# Gameboy_Pocket.net
KiCad netlist of a schematic drawn in EAGLE
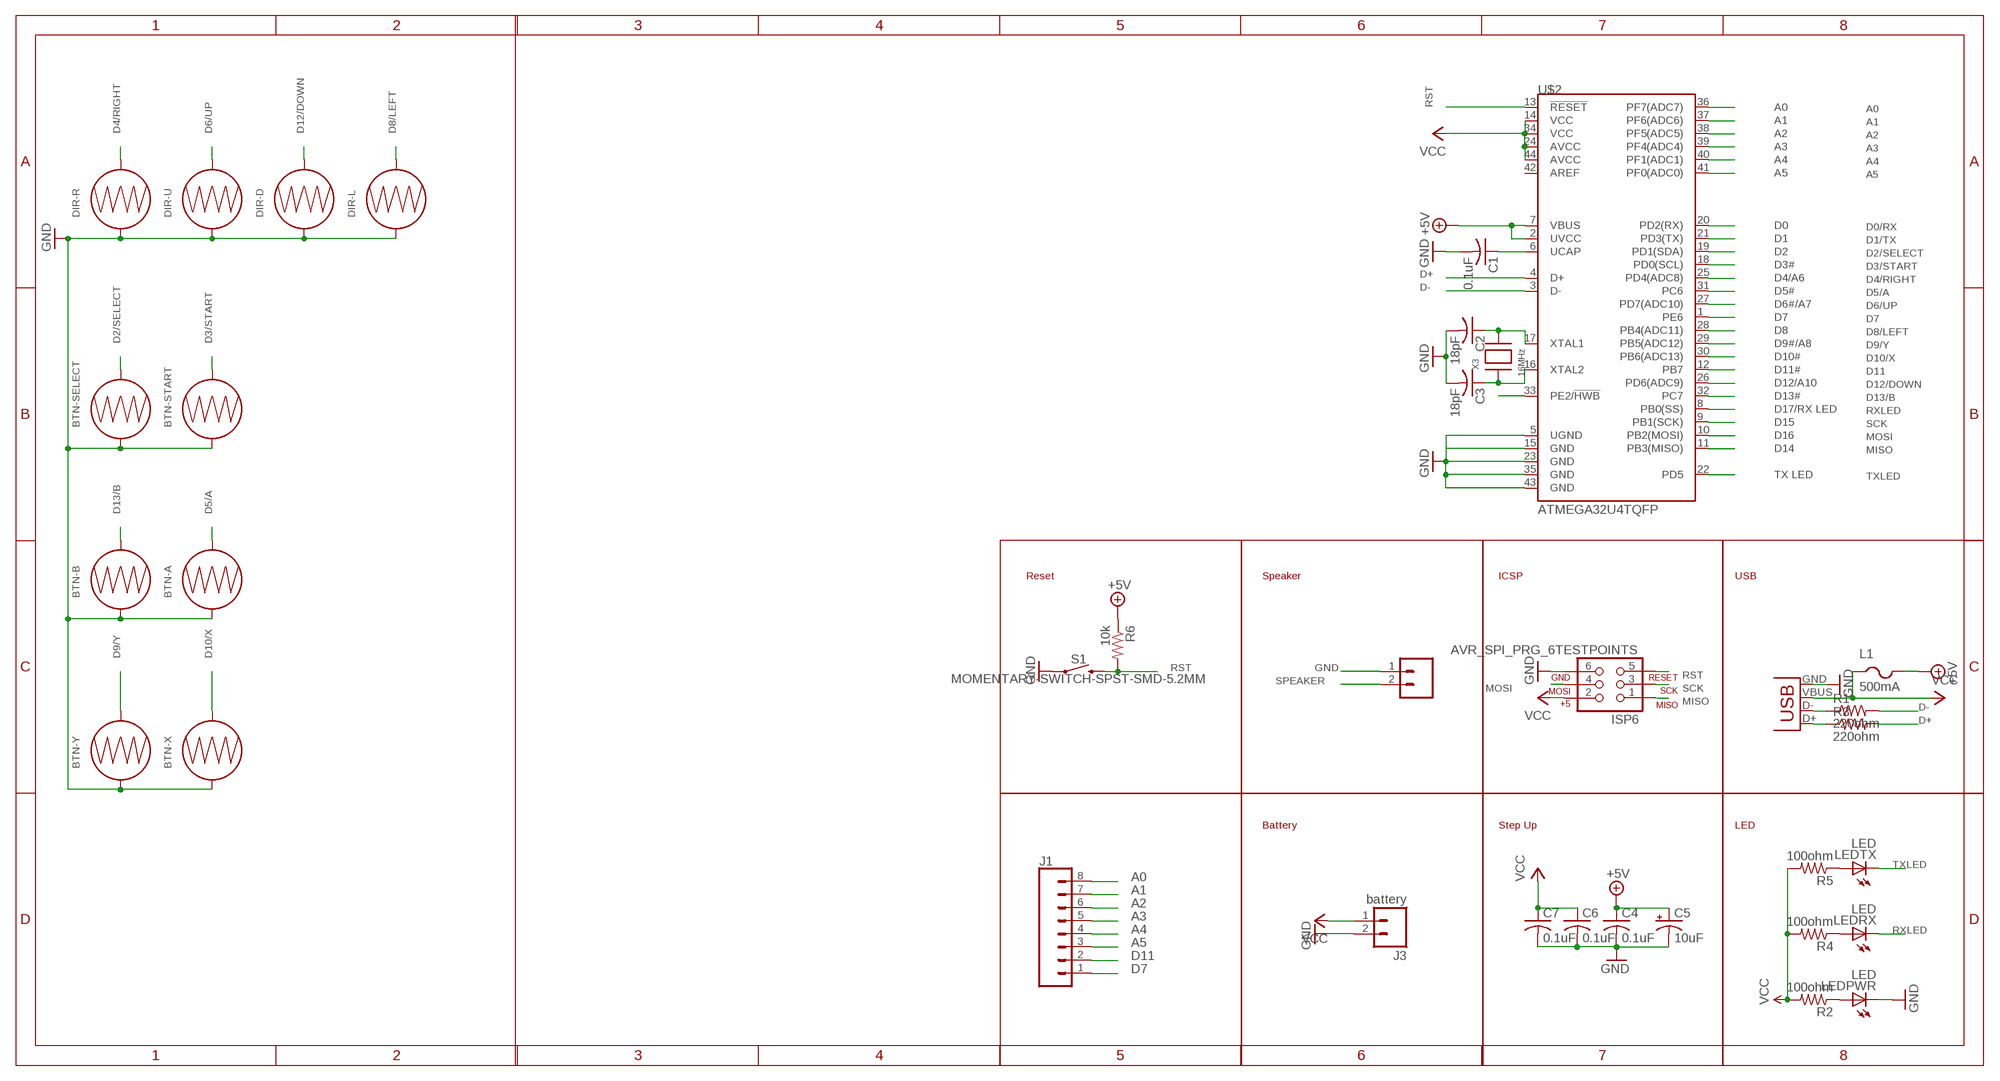
[diagram p0: schematic, sheet 1]

(export (version "E")
  (design (tool "Eeschema 10.0.6"))
  (components
    (comp (ref "BTN-A")
      (value "BUTTON-CONDUCTIVESMD")
      (footprint "eagle-import:BUTTON-CONDUCTIVE")
      (libsource (lib "eagle-import") (part "BUTTON-CONDUCTIVESMD"))
    )
    (comp (ref "BTN-B")
      (value "BUTTON-CONDUCTIVESMD")
      (footprint "eagle-import:BUTTON-CONDUCTIVE")
      (libsource (lib "eagle-import") (part "BUTTON-CONDUCTIVESMD"))
    )
    (comp (ref "BTN-SELECT")
      (value "BUTTON-CONDUCTIVESMD")
      (footprint "eagle-import:BUTTON-CONDUCTIVE")
      (libsource (lib "eagle-import") (part "BUTTON-CONDUCTIVESMD"))
    )
    (comp (ref "BTN-START")
      (value "BUTTON-CONDUCTIVESMD")
      (footprint "eagle-import:BUTTON-CONDUCTIVE")
      (libsource (lib "eagle-import") (part "BUTTON-CONDUCTIVESMD"))
    )
    (comp (ref "BTN-X")
      (value "BUTTON-CONDUCTIVESMD")
      (footprint "eagle-import:BUTTON-CONDUCTIVE")
      (libsource (lib "eagle-import") (part "BUTTON-CONDUCTIVESMD"))
    )
    (comp (ref "BTN-Y")
      (value "BUTTON-CONDUCTIVESMD")
      (footprint "eagle-import:BUTTON-CONDUCTIVE")
      (libsource (lib "eagle-import") (part "BUTTON-CONDUCTIVESMD"))
    )
    (comp (ref "C1")
      (value "0.1uF")
      (footprint "eagle-import:C0805")
      (libsource (lib "eagle-import") (part "C-USC0805"))
    )
    (comp (ref "C2")
      (value "18pF")
      (footprint "eagle-import:C0805")
      (libsource (lib "eagle-import") (part "C-USC0805"))
    )
    (comp (ref "C3")
      (value "18pF")
      (footprint "eagle-import:C0805")
      (libsource (lib "eagle-import") (part "C-USC0805"))
    )
    (comp (ref "C4")
      (value "0.1uF")
      (footprint "eagle-import:C0805")
      (libsource (lib "eagle-import") (part "C-USC0805"))
    )
    (comp (ref "C5")
      (value "10uF")
      (footprint "eagle-import:EIA3216")
      (libsource (lib "eagle-import") (part "10UF-TANT"))
    )
    (comp (ref "C6")
      (value "0.1uF")
      (footprint "eagle-import:C0805")
      (libsource (lib "eagle-import") (part "C-USC0805"))
    )
    (comp (ref "C7")
      (value "0.1uF")
      (footprint "eagle-import:C0805")
      (libsource (lib "eagle-import") (part "C-USC0805"))
    )
    (comp (ref "CN1")
      (value "USB-SMD-NS")
      (footprint "eagle-import:USB-MINIB-NOSTOP")
      (libsource (lib "eagle-import") (part "USB-SMD-NS"))
    )
    (comp (ref "DIR-D")
      (value "BUTTON-CONDUCTIVESMD")
      (footprint "eagle-import:BUTTON-CONDUCTIVE")
      (libsource (lib "eagle-import") (part "BUTTON-CONDUCTIVESMD"))
    )
    (comp (ref "DIR-L")
      (value "BUTTON-CONDUCTIVESMD")
      (footprint "eagle-import:BUTTON-CONDUCTIVE")
      (libsource (lib "eagle-import") (part "BUTTON-CONDUCTIVESMD"))
    )
    (comp (ref "DIR-R")
      (value "BUTTON-CONDUCTIVESMD")
      (footprint "eagle-import:BUTTON-CONDUCTIVE")
      (libsource (lib "eagle-import") (part "BUTTON-CONDUCTIVESMD"))
    )
    (comp (ref "DIR-U")
      (value "BUTTON-CONDUCTIVESMD")
      (footprint "eagle-import:BUTTON-CONDUCTIVE")
      (libsource (lib "eagle-import") (part "BUTTON-CONDUCTIVESMD"))
    )
    (comp (ref "ISP6")
      (value "AVR_SPI_PRG_6TESTPOINTS")
      (footprint "eagle-import:2X3_TEST_POINTS")
      (libsource (lib "eagle-import") (part "AVR_SPI_PRG_6TESTPOINTS"))
    )
    (comp (ref "J1")
      (value "CONN_08NO_SILK_FEMALE_PTH")
      (footprint "eagle-import:1X08_NO_SILK")
      (libsource (lib "eagle-import") (part "CONN_08NO_SILK_FEMALE_PTH"))
    )
    (comp (ref "J3")
      (value "battery")
      (footprint "eagle-import:JST-2-PTH-VERT")
      (libsource (lib "eagle-import") (part "M02JST-PTH-VERT"))
    )
    (comp (ref "JP2")
      (value "M02PTH")
      (footprint "eagle-import:1X02")
      (libsource (lib "eagle-import") (part "M02PTH"))
    )
    (comp (ref "L1")
      (value "500mA")
      (footprint "eagle-import:R1206")
      (libsource (lib "eagle-import") (part "PTCFUSE-1206"))
    )
    (comp (ref "LEDPWR")
      (value "LED")
      (footprint "eagle-import:CHIPLED_0805")
      (libsource (lib "eagle-import") (part "LEDCHIPLED_0805"))
    )
    (comp (ref "LEDRX")
      (value "LED")
      (footprint "eagle-import:CHIPLED_0805")
      (libsource (lib "eagle-import") (part "LEDCHIPLED_0805"))
    )
    (comp (ref "LEDTX")
      (value "LED")
      (footprint "eagle-import:CHIPLED_0805")
      (libsource (lib "eagle-import") (part "LEDCHIPLED_0805"))
    )
    (comp (ref "R1")
      (value "220ohm")
      (footprint "eagle-import:R0805")
      (libsource (lib "eagle-import") (part "R-US_R0805"))
    )
    (comp (ref "R2")
      (value "100ohm")
      (footprint "eagle-import:R0805")
      (libsource (lib "eagle-import") (part "R-US_R0805"))
    )
    (comp (ref "R3")
      (value "220ohm")
      (footprint "eagle-import:R0805")
      (libsource (lib "eagle-import") (part "R-US_R0805"))
    )
    (comp (ref "R4")
      (value "100ohm")
      (footprint "eagle-import:R0805")
      (libsource (lib "eagle-import") (part "R-US_R0805"))
    )
    (comp (ref "R5")
      (value "100ohm")
      (footprint "eagle-import:R0805")
      (libsource (lib "eagle-import") (part "R-US_R0805"))
    )
    (comp (ref "R6")
      (value "10k")
      (footprint "eagle-import:R0805")
      (libsource (lib "eagle-import") (part "R-US_R0805"))
    )
    (comp (ref "S1")
      (value "MOMENTARY-SWITCH-SPST-SMD-5.2MM")
      (footprint "eagle-import:TACTILE_SWITCH_SMD_5.2MM")
      (libsource (lib "eagle-import") (part "MOMENTARY-SWITCH-SPST-SMD-5.2MM"))
    )
    (comp (ref "U$2")
      (value "ATMEGA32U4TQFP")
      (footprint "eagle-import:SPARKFUN-DIGITALIC_TQFP44")
      (libsource (lib "eagle-import") (part "ATMEGA32U4TQFP"))
    )
    (comp (ref "X3")
      (value "16MHz")
      (footprint "eagle-import:NX5032")
      (libsource (lib "eagle-import") (part "XTALNX5032"))
    )
  )
  (nets
    (net (code "1") (name "+5V") (class "Default")
      (node (ref "C4") (pin "1") (pinfunction "1_1") (pintype "passive"))
      (node (ref "C5") (pin "A") (pinfunction "+_A") (pintype "passive"))
      (node (ref "L1") (pin "2") (pinfunction "2_2") (pintype "passive"))
      (node (ref "R6") (pin "1") (pinfunction "1_1") (pintype "passive"))
      (node (ref "U$2") (pin "2") (pinfunction "UVCC_2") (pintype "bidirectional"))
      (node (ref "U$2") (pin "7") (pinfunction "VBUS_7") (pintype "bidirectional"))
    )
    (net (code "2") (name "/A0") (class "Default")
      (node (ref "J1") (pin "8") (pinfunction "8_8") (pintype "passive"))
      (node (ref "U$2") (pin "36") (pinfunction "PF7(ADC7)_36") (pintype "bidirectional"))
    )
    (net (code "3") (name "/A1") (class "Default")
      (node (ref "J1") (pin "7") (pinfunction "7_7") (pintype "passive"))
      (node (ref "U$2") (pin "37") (pinfunction "PF6(ADC6)_37") (pintype "bidirectional"))
    )
    (net (code "4") (name "/A2") (class "Default")
      (node (ref "J1") (pin "6") (pinfunction "6_6") (pintype "passive"))
      (node (ref "U$2") (pin "38") (pinfunction "PF5(ADC5)_38") (pintype "bidirectional"))
    )
    (net (code "5") (name "/A3") (class "Default")
      (node (ref "J1") (pin "5") (pinfunction "5_5") (pintype "passive"))
      (node (ref "U$2") (pin "39") (pinfunction "PF4(ADC4)_39") (pintype "bidirectional"))
    )
    (net (code "6") (name "/A4") (class "Default")
      (node (ref "J1") (pin "4") (pinfunction "4_4") (pintype "passive"))
      (node (ref "U$2") (pin "40") (pinfunction "PF1(ADC1)_40") (pintype "bidirectional"))
    )
    (net (code "7") (name "/A5") (class "Default")
      (node (ref "J1") (pin "3") (pinfunction "3_3") (pintype "passive"))
      (node (ref "U$2") (pin "41") (pinfunction "PF0(ADC0)_41") (pintype "bidirectional"))
    )
    (net (code "8") (name "/D+") (class "Default")
      (node (ref "R3") (pin "2") (pinfunction "2_2") (pintype "passive"))
      (node (ref "U$2") (pin "4") (pinfunction "D+_4") (pintype "bidirectional"))
    )
    (net (code "9") (name "/D-") (class "Default")
      (node (ref "R1") (pin "2") (pinfunction "2_2") (pintype "passive"))
      (node (ref "U$2") (pin "3") (pinfunction "D-_3") (pintype "bidirectional"))
    )
    (net (code "10") (name "/D0{slash}RX") (class "Default")
      (node (ref "U$2") (pin "20") (pinfunction "PD2(RX)_20") (pintype "bidirectional"))
    )
    (net (code "11") (name "/D1{slash}TX") (class "Default")
      (node (ref "U$2") (pin "21") (pinfunction "PD3(TX)_21") (pintype "bidirectional"))
    )
    (net (code "12") (name "/D2{slash}SELECT") (class "Default")
      (node (ref "BTN-SELECT") (pin "2") (pinfunction "2_2") (pintype "passive"))
      (node (ref "U$2") (pin "19") (pinfunction "PD1(SDA)_19") (pintype "bidirectional"))
    )
    (net (code "13") (name "/D3{slash}START") (class "Default")
      (node (ref "BTN-START") (pin "2") (pinfunction "2_2") (pintype "passive"))
      (node (ref "U$2") (pin "18") (pinfunction "PD0(SCL)_18") (pintype "bidirectional"))
    )
    (net (code "14") (name "/D4{slash}RIGHT") (class "Default")
      (node (ref "DIR-R") (pin "2") (pinfunction "2_2") (pintype "passive"))
      (node (ref "U$2") (pin "25") (pinfunction "PD4(ADC8)_25") (pintype "bidirectional"))
    )
    (net (code "15") (name "/D5{slash}A") (class "Default")
      (node (ref "BTN-A") (pin "2") (pinfunction "2_2") (pintype "passive"))
      (node (ref "U$2") (pin "31") (pinfunction "PC6_31") (pintype "bidirectional"))
    )
    (net (code "16") (name "/D6{slash}UP") (class "Default")
      (node (ref "DIR-U") (pin "2") (pinfunction "2_2") (pintype "passive"))
      (node (ref "U$2") (pin "27") (pinfunction "PD7(ADC10)_27") (pintype "bidirectional"))
    )
    (net (code "17") (name "/D7") (class "Default")
      (node (ref "J1") (pin "1") (pinfunction "1_1") (pintype "passive"))
      (node (ref "U$2") (pin "1") (pinfunction "PE6_1") (pintype "bidirectional"))
    )
    (net (code "18") (name "/D8{slash}LEFT") (class "Default")
      (node (ref "DIR-L") (pin "2") (pinfunction "2_2") (pintype "passive"))
      (node (ref "U$2") (pin "28") (pinfunction "PB4(ADC11)_28") (pintype "bidirectional"))
    )
    (net (code "19") (name "/D9{slash}Y") (class "Default")
      (node (ref "BTN-Y") (pin "2") (pinfunction "2_2") (pintype "passive"))
      (node (ref "U$2") (pin "29") (pinfunction "PB5(ADC12)_29") (pintype "bidirectional"))
    )
    (net (code "20") (name "/D10{slash}X") (class "Default")
      (node (ref "BTN-X") (pin "2") (pinfunction "2_2") (pintype "passive"))
      (node (ref "U$2") (pin "30") (pinfunction "PB6(ADC13)_30") (pintype "bidirectional"))
    )
    (net (code "21") (name "/D11") (class "Default")
      (node (ref "J1") (pin "2") (pinfunction "2_2") (pintype "passive"))
      (node (ref "U$2") (pin "12") (pinfunction "PB7_12") (pintype "bidirectional"))
    )
    (net (code "22") (name "/D12{slash}DOWN") (class "Default")
      (node (ref "DIR-D") (pin "2") (pinfunction "2_2") (pintype "passive"))
      (node (ref "U$2") (pin "26") (pinfunction "PD6(ADC9)_26") (pintype "bidirectional"))
    )
    (net (code "23") (name "/D13{slash}B") (class "Default")
      (node (ref "BTN-B") (pin "2") (pinfunction "2_2") (pintype "passive"))
      (node (ref "U$2") (pin "32") (pinfunction "PC7_32") (pintype "bidirectional"))
    )
    (net (code "24") (name "/MISO") (class "Default")
      (node (ref "ISP6") (pin "1") (pinfunction "1_1") (pintype "passive"))
      (node (ref "U$2") (pin "11") (pinfunction "PB3(MISO)_11") (pintype "bidirectional"))
    )
    (net (code "25") (name "/MOSI") (class "Default")
      (node (ref "ISP6") (pin "4") (pinfunction "4_4") (pintype "passive"))
      (node (ref "U$2") (pin "10") (pinfunction "PB2(MOSI)_10") (pintype "bidirectional"))
    )
    (net (code "26") (name "/RST") (class "Default")
      (node (ref "ISP6") (pin "5") (pinfunction "5_5") (pintype "passive"))
      (node (ref "R6") (pin "2") (pinfunction "2_2") (pintype "passive"))
      (node (ref "S1") (pin "3") (pinfunction "2_3") (pintype "passive"))
      (node (ref "U$2") (pin "13") (pinfunction "~{RESET}_13") (pintype "bidirectional"))
    )
    (net (code "27") (name "/RXLED") (class "Default")
      (node (ref "LEDRX") (pin "C") (pinfunction "C_C") (pintype "passive"))
      (node (ref "U$2") (pin "8") (pinfunction "PB0(SS)_8") (pintype "bidirectional"))
    )
    (net (code "28") (name "/SCK") (class "Default")
      (node (ref "ISP6") (pin "3") (pinfunction "3_3") (pintype "passive"))
      (node (ref "U$2") (pin "9") (pinfunction "PB1(SCK)_9") (pintype "bidirectional"))
    )
    (net (code "29") (name "/SPEAKER") (class "Default")
      (node (ref "JP2") (pin "2") (pinfunction "2_2") (pintype "passive"))
    )
    (net (code "30") (name "/TXLED") (class "Default")
      (node (ref "LEDTX") (pin "C") (pinfunction "C_C") (pintype "passive"))
      (node (ref "U$2") (pin "22") (pinfunction "PD5_22") (pintype "bidirectional"))
    )
    (net (code "31") (name "GND") (class "Default")
      (node (ref "BTN-A") (pin "1") (pinfunction "1_1") (pintype "passive"))
      (node (ref "BTN-B") (pin "1") (pinfunction "1_1") (pintype "passive"))
      (node (ref "BTN-SELECT") (pin "1") (pinfunction "1_1") (pintype "passive"))
      (node (ref "BTN-START") (pin "1") (pinfunction "1_1") (pintype "passive"))
      (node (ref "BTN-X") (pin "1") (pinfunction "1_1") (pintype "passive"))
      (node (ref "BTN-Y") (pin "1") (pinfunction "1_1") (pintype "passive"))
      (node (ref "C1") (pin "2") (pinfunction "2_2") (pintype "passive"))
      (node (ref "C2") (pin "2") (pinfunction "2_2") (pintype "passive"))
      (node (ref "C3") (pin "2") (pinfunction "2_2") (pintype "passive"))
      (node (ref "C4") (pin "2") (pinfunction "2_2") (pintype "passive"))
      (node (ref "C5") (pin "C") (pinfunction "-_C") (pintype "passive"))
      (node (ref "C6") (pin "2") (pinfunction "2_2") (pintype "passive"))
      (node (ref "C7") (pin "2") (pinfunction "2_2") (pintype "passive"))
      (node (ref "CN1") (pin "GND") (pinfunction "GND_GND") (pintype "bidirectional"))
      (node (ref "DIR-D") (pin "1") (pinfunction "1_1") (pintype "passive"))
      (node (ref "DIR-L") (pin "1") (pinfunction "1_1") (pintype "passive"))
      (node (ref "DIR-R") (pin "1") (pinfunction "1_1") (pintype "passive"))
      (node (ref "DIR-U") (pin "1") (pinfunction "1_1") (pintype "passive"))
      (node (ref "ISP6") (pin "6") (pinfunction "6_6") (pintype "passive"))
      (node (ref "J3") (pin "2") (pinfunction "2_2") (pintype "passive"))
      (node (ref "JP2") (pin "1") (pinfunction "1_1") (pintype "passive"))
      (node (ref "LEDPWR") (pin "C") (pinfunction "C_C") (pintype "passive"))
      (node (ref "S1") (pin "1") (pinfunction "1_1") (pintype "passive"))
      (node (ref "U$2") (pin "15") (pinfunction "GND_15") (pintype "bidirectional"))
      (node (ref "U$2") (pin "23") (pinfunction "GND_23") (pintype "bidirectional"))
      (node (ref "U$2") (pin "35") (pinfunction "GND_35") (pintype "bidirectional"))
      (node (ref "U$2") (pin "43") (pinfunction "GND_43") (pintype "bidirectional"))
      (node (ref "U$2") (pin "5") (pinfunction "UGND_5") (pintype "bidirectional"))
    )
    (net (code "32") (name "Net-(CN1-PadD+)") (class "Default")
      (node (ref "CN1") (pin "D+") (pinfunction "D+_D+") (pintype "bidirectional"))
      (node (ref "R3") (pin "1") (pinfunction "1_1") (pintype "passive"))
    )
    (net (code "33") (name "Net-(CN1-PadD-)") (class "Default")
      (node (ref "CN1") (pin "D-") (pinfunction "D-_D-") (pintype "bidirectional"))
      (node (ref "R1") (pin "1") (pinfunction "1_1") (pintype "passive"))
    )
    (net (code "34") (name "Net-(LEDPWR-PadA)") (class "Default")
      (node (ref "LEDPWR") (pin "A") (pinfunction "A_A") (pintype "passive"))
      (node (ref "R2") (pin "1") (pinfunction "1_1") (pintype "passive"))
    )
    (net (code "35") (name "Net-(LEDRX-PadA)") (class "Default")
      (node (ref "LEDRX") (pin "A") (pinfunction "A_A") (pintype "passive"))
      (node (ref "R4") (pin "1") (pinfunction "1_1") (pintype "passive"))
    )
    (net (code "36") (name "Net-(LEDTX-PadA)") (class "Default")
      (node (ref "LEDTX") (pin "A") (pinfunction "A_A") (pintype "passive"))
      (node (ref "R5") (pin "1") (pinfunction "1_1") (pintype "passive"))
    )
    (net (code "37") (name "Net-(U$2-UCAP)") (class "Default")
      (node (ref "C1") (pin "1") (pinfunction "1_1") (pintype "passive"))
      (node (ref "U$2") (pin "6") (pinfunction "UCAP_6") (pintype "bidirectional"))
    )
    (net (code "38") (name "Net-(U$2-XTAL1)") (class "Default")
      (node (ref "C2") (pin "1") (pinfunction "1_1") (pintype "passive"))
      (node (ref "U$2") (pin "17") (pinfunction "XTAL1_17") (pintype "bidirectional"))
      (node (ref "X3") (pin "P$2") (pinfunction "P$2_P$2") (pintype "bidirectional"))
    )
    (net (code "39") (name "Net-(U$2-XTAL2)") (class "Default")
      (node (ref "C3") (pin "1") (pinfunction "1_1") (pintype "passive"))
      (node (ref "U$2") (pin "16") (pinfunction "XTAL2_16") (pintype "bidirectional"))
      (node (ref "X3") (pin "P$1") (pinfunction "P$1_P$1") (pintype "bidirectional"))
    )
    (net (code "40") (name "VCC") (class "Default")
      (node (ref "C6") (pin "1") (pinfunction "1_1") (pintype "passive"))
      (node (ref "C7") (pin "1") (pinfunction "1_1") (pintype "passive"))
      (node (ref "CN1") (pin "VBUS") (pinfunction "VBUS_VBUS") (pintype "bidirectional"))
      (node (ref "ISP6") (pin "2") (pinfunction "2_2") (pintype "passive"))
      (node (ref "J3") (pin "1") (pinfunction "1_1") (pintype "passive"))
      (node (ref "L1") (pin "1") (pinfunction "1_1") (pintype "passive"))
      (node (ref "R2") (pin "2") (pinfunction "2_2") (pintype "passive"))
      (node (ref "R4") (pin "2") (pinfunction "2_2") (pintype "passive"))
      (node (ref "R5") (pin "2") (pinfunction "2_2") (pintype "passive"))
      (node (ref "U$2") (pin "14") (pinfunction "VCC_14") (pintype "bidirectional"))
      (node (ref "U$2") (pin "24") (pinfunction "AVCC_24") (pintype "bidirectional"))
      (node (ref "U$2") (pin "34") (pinfunction "VCC_34") (pintype "bidirectional"))
      (node (ref "U$2") (pin "44") (pinfunction "AVCC_44") (pintype "bidirectional"))
    )
    (net (code "41") (name "unconnected-(U$2-AREF-Pad42)") (class "Default")
      (node (ref "U$2") (pin "42") (pinfunction "AREF_42") (pintype "bidirectional"))
    )
    (net (code "42") (name "unconnected-(U$2-PE2{slash}~{HWB}-Pad33)") (class "Default")
      (node (ref "U$2") (pin "33") (pinfunction "PE2/~{HWB}_33") (pintype "bidirectional"))
    )
  )
)
